# Airowl_Schematic.net
KiCad netlist of a schematic drawn in EAGLE
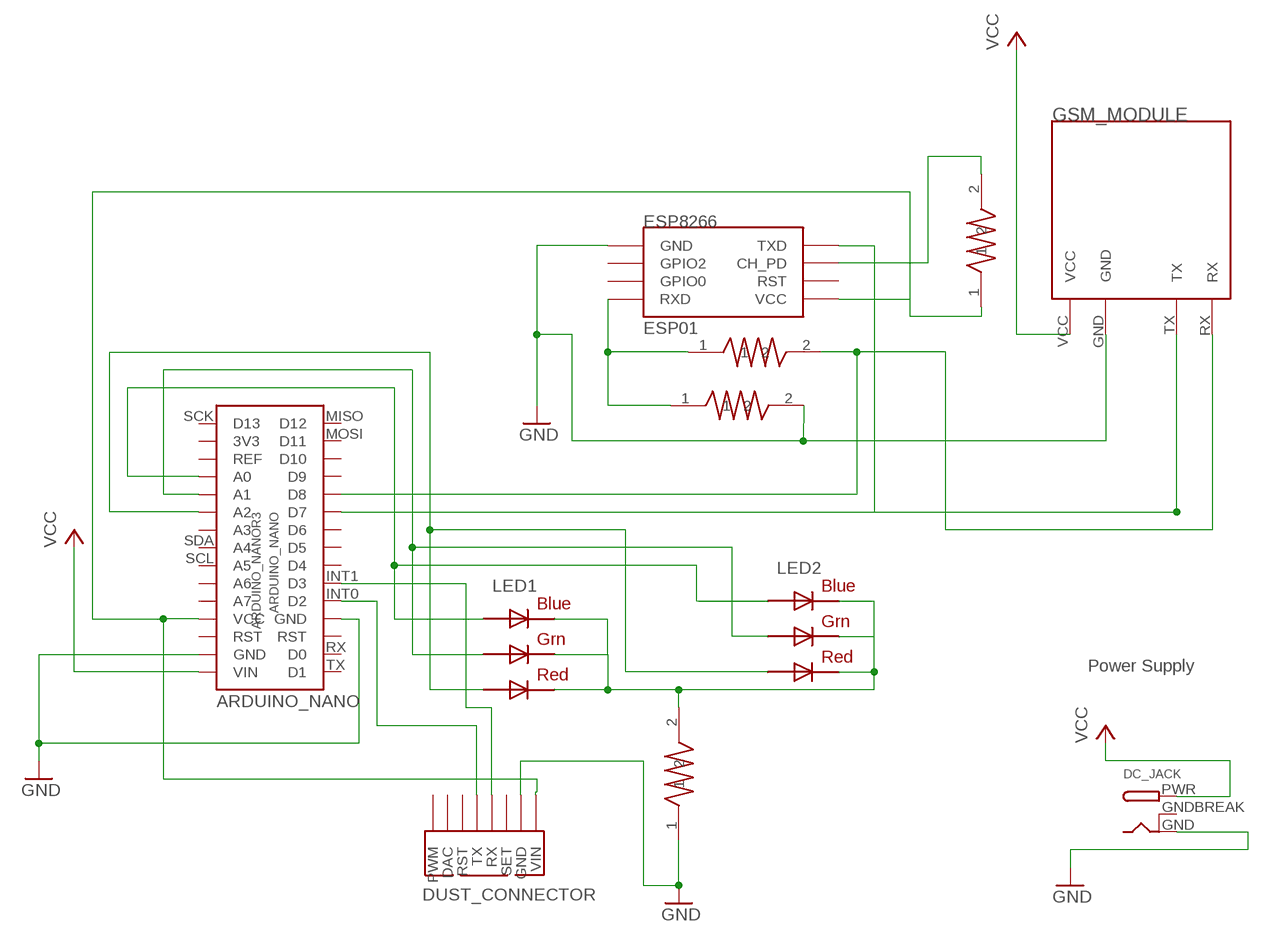
[diagram p0: schematic, sheet 1]

(export (version "E")
  (design (tool "Eeschema 10.0.6"))
  (components
    (comp (ref "ARDUINO_NANO")
      (value "ARDUINO_NANOR3")
      (footprint "eagle-import:ARDUINO-NANO")
      (libsource (lib "eagle-import") (part "ARDUINO_NANOR3"))
    )
    (comp (ref "DC_JACK")
      (value "DCBARRELPTH")
      (footprint "eagle-import:DCJACK_2MM_PTH")
      (libsource (lib "eagle-import") (part "DCBARRELPTH"))
    )
    (comp (ref "DUST_CONNECTOR")
      (value "WINSEN_CONNECTOR")
      (footprint "eagle-import:WINSEN_CONNECTOR")
      (libsource (lib "eagle-import") (part "WINSEN_CONNECTOR"))
    )
    (comp (ref "ESP8266")
      (value "ESP01")
      (footprint "eagle-import:ESP01")
      (libsource (lib "eagle-import") (part "ESP01"))
    )
    (comp (ref "GSM_MODULE")
      (value "GSM900_MODULE")
      (footprint "eagle-import:GSM900_MODULE")
      (libsource (lib "eagle-import") (part "GSM900_MODULE"))
    )
    (comp (ref "LED1")
      (value "RGBLED5050")
      (footprint "eagle-import:RGBLED5050")
      (libsource (lib "eagle-import") (part "RGBLED5050"))
    )
    (comp (ref "LED2")
      (value "RGBLED5050")
      (footprint "eagle-import:RGBLED5050")
      (libsource (lib "eagle-import") (part "RGBLED5050"))
    )
    (comp (ref "R1")
      (value "RESISTOR(HORIZONTAL)")
      (footprint "eagle-import:RESISTER(HORIZONTAL)")
      (libsource (lib "eagle-import") (part "RESISTOR(HORIZONTAL)"))
    )
    (comp (ref "R2")
      (value "RESISTOR(HORIZONTAL)")
      (footprint "eagle-import:RESISTER(HORIZONTAL)")
      (libsource (lib "eagle-import") (part "RESISTOR(HORIZONTAL)"))
    )
    (comp (ref "R3")
      (value "RESISTOR(HORIZONTAL)")
      (footprint "eagle-import:RESISTER(HORIZONTAL)")
      (libsource (lib "eagle-import") (part "RESISTOR(HORIZONTAL)"))
    )
    (comp (ref "R4")
      (value "RESISTOR(HORIZONTAL)")
      (footprint "eagle-import:RESISTER(HORIZONTAL)")
      (libsource (lib "eagle-import") (part "RESISTOR(HORIZONTAL)"))
    )
  )
  (nets
    (net (code "1") (name "/3V3") (class "Default")
      (node (ref "ARDUINO_NANO") (pin "3V3") (pinfunction "3V3_3V3") (pintype "power_in"))
    )
    (net (code "2") (name "/GNDBREAK") (class "Default")
      (node (ref "DC_JACK") (pin "GNDBREAK") (pinfunction "GNDBREAK_GNDBREAK") (pintype "power_in"))
    )
    (net (code "3") (name "GND") (class "Default")
      (node (ref "ARDUINO_NANO") (pin "GND@1") (pinfunction "GND_GND@1") (pintype "power_in"))
      (node (ref "ARDUINO_NANO") (pin "GND@2") (pinfunction "GND_GND@2") (pintype "power_in"))
      (node (ref "DC_JACK") (pin "GND") (pinfunction "GND_GND") (pintype "power_in"))
      (node (ref "DUST_CONNECTOR") (pin "P$8") (pinfunction "GND_P$8") (pintype "bidirectional"))
      (node (ref "ESP8266") (pin "GND") (pinfunction "GND_GND") (pintype "bidirectional"))
      (node (ref "GSM_MODULE") (pin "GND") (pinfunction "GND_GND") (pintype "bidirectional"))
      (node (ref "R1") (pin "1") (pinfunction "1_1") (pintype "bidirectional"))
      (node (ref "R3") (pin "2") (pinfunction "2_2") (pintype "bidirectional"))
    )
    (net (code "4") (name "Net-(ARDUINO_NANO-D2)") (class "Default")
      (node (ref "ARDUINO_NANO") (pin "INT0") (pinfunction "D2_INT0") (pintype "bidirectional"))
      (node (ref "DUST_CONNECTOR") (pin "P$5") (pinfunction "TX_P$5") (pintype "bidirectional"))
    )
    (net (code "5") (name "Net-(ARDUINO_NANO-D3)") (class "Default")
      (node (ref "ARDUINO_NANO") (pin "INT1") (pinfunction "D3_INT1") (pintype "bidirectional"))
      (node (ref "DUST_CONNECTOR") (pin "P$6") (pinfunction "RX_P$6") (pintype "bidirectional"))
    )
    (net (code "6") (name "Net-(ARDUINO_NANO-PadD8)") (class "Default")
      (node (ref "ARDUINO_NANO") (pin "D8") (pinfunction "D8_D8") (pintype "bidirectional"))
      (node (ref "GSM_MODULE") (pin "RX") (pinfunction "RX_RX") (pintype "bidirectional"))
      (node (ref "R2") (pin "2") (pinfunction "2_2") (pintype "bidirectional"))
    )
    (net (code "7") (name "Net-(DUST_CONNECTOR-VIN)") (class "Default")
      (node (ref "ARDUINO_NANO") (pin "VCC") (pinfunction "VCC_VCC") (pintype "power_in"))
      (node (ref "DUST_CONNECTOR") (pin "P$9") (pinfunction "VIN_P$9") (pintype "bidirectional"))
      (node (ref "ESP8266") (pin "VCC") (pinfunction "VCC_VCC") (pintype "bidirectional"))
      (node (ref "R4") (pin "1") (pinfunction "1_1") (pintype "bidirectional"))
    )
    (net (code "8") (name "Net-(ESP8266-PadCH_PD)") (class "Default")
      (node (ref "ESP8266") (pin "CH_PD") (pinfunction "CH_PD_CH_PD") (pintype "bidirectional"))
      (node (ref "R4") (pin "2") (pinfunction "2_2") (pintype "bidirectional"))
    )
    (net (code "9") (name "Net-(ESP8266-RXD)") (class "Default")
      (node (ref "ESP8266") (pin "RX") (pinfunction "RXD_RX") (pintype "bidirectional"))
      (node (ref "R2") (pin "1") (pinfunction "1_1") (pintype "bidirectional"))
      (node (ref "R3") (pin "1") (pinfunction "1_1") (pintype "bidirectional"))
    )
    (net (code "10") (name "Net-(ESP8266-TXD)") (class "Default")
      (node (ref "ARDUINO_NANO") (pin "D7") (pinfunction "D7_D7") (pintype "bidirectional"))
      (node (ref "ESP8266") (pin "TX") (pinfunction "TXD_TX") (pintype "bidirectional"))
      (node (ref "GSM_MODULE") (pin "TX") (pinfunction "TX_TX") (pintype "bidirectional"))
    )
    (net (code "11") (name "Net-(LED1-BLUE_A)") (class "Default")
      (node (ref "ARDUINO_NANO") (pin "A0") (pinfunction "A0_A0") (pintype "bidirectional"))
      (node (ref "LED1") (pin "3") (pinfunction "BLUE_A_3") (pintype "bidirectional"))
      (node (ref "LED2") (pin "3") (pinfunction "BLUE_A_3") (pintype "bidirectional"))
    )
    (net (code "12") (name "Net-(LED1-BLUE_C)") (class "Default")
      (node (ref "LED1") (pin "4") (pinfunction "BLUE_C_4") (pintype "bidirectional"))
      (node (ref "LED1") (pin "5") (pinfunction "RED_C_5") (pintype "bidirectional"))
      (node (ref "LED1") (pin "6") (pinfunction "GREEN_C_6") (pintype "bidirectional"))
      (node (ref "LED2") (pin "4") (pinfunction "BLUE_C_4") (pintype "bidirectional"))
      (node (ref "LED2") (pin "5") (pinfunction "RED_C_5") (pintype "bidirectional"))
      (node (ref "LED2") (pin "6") (pinfunction "GREEN_C_6") (pintype "bidirectional"))
    )
    (net (code "13") (name "Net-(LED1-GREEN_A)") (class "Default")
      (node (ref "ARDUINO_NANO") (pin "A1") (pinfunction "A1_A1") (pintype "bidirectional"))
      (node (ref "LED1") (pin "1") (pinfunction "GREEN_A_1") (pintype "bidirectional"))
      (node (ref "LED2") (pin "1") (pinfunction "GREEN_A_1") (pintype "bidirectional"))
    )
    (net (code "14") (name "Net-(LED1-RED_A)") (class "Default")
      (node (ref "ARDUINO_NANO") (pin "A2") (pinfunction "A2_A2") (pintype "bidirectional"))
      (node (ref "LED1") (pin "2") (pinfunction "RED_A_2") (pintype "bidirectional"))
      (node (ref "LED2") (pin "2") (pinfunction "RED_A_2") (pintype "bidirectional"))
    )
    (net (code "15") (name "VCC") (class "Default")
      (node (ref "ARDUINO_NANO") (pin "VIN") (pinfunction "VIN_VIN") (pintype "power_in"))
      (node (ref "DC_JACK") (pin "PWR") (pinfunction "PWR_PWR") (pintype "power_in"))
      (node (ref "GSM_MODULE") (pin "VCC") (pinfunction "VCC_VCC") (pintype "bidirectional"))
    )
    (net (code "16") (name "unconnected-(ARDUINO_NANO-A4-PadSDA)") (class "Default")
      (node (ref "ARDUINO_NANO") (pin "SDA") (pinfunction "A4_SDA") (pintype "bidirectional"))
    )
    (net (code "17") (name "unconnected-(ARDUINO_NANO-A5-PadSCL)") (class "Default")
      (node (ref "ARDUINO_NANO") (pin "SCL") (pinfunction "A5_SCL") (pintype "bidirectional"))
    )
    (net (code "18") (name "unconnected-(ARDUINO_NANO-D0-PadRX)") (class "Default")
      (node (ref "ARDUINO_NANO") (pin "RX") (pinfunction "D0_RX") (pintype "bidirectional"))
    )
    (net (code "19") (name "unconnected-(ARDUINO_NANO-D1-PadTX)") (class "Default")
      (node (ref "ARDUINO_NANO") (pin "TX") (pinfunction "D1_TX") (pintype "bidirectional"))
    )
    (net (code "20") (name "unconnected-(ARDUINO_NANO-D11-PadMOSI)") (class "Default")
      (node (ref "ARDUINO_NANO") (pin "MOSI") (pinfunction "D11_MOSI") (pintype "bidirectional"))
    )
    (net (code "21") (name "unconnected-(ARDUINO_NANO-D12-PadMISO)") (class "Default")
      (node (ref "ARDUINO_NANO") (pin "MISO") (pinfunction "D12_MISO") (pintype "bidirectional"))
    )
    (net (code "22") (name "unconnected-(ARDUINO_NANO-D13-PadSCK)") (class "Default")
      (node (ref "ARDUINO_NANO") (pin "SCK") (pinfunction "D13_SCK") (pintype "bidirectional"))
    )
    (net (code "23") (name "unconnected-(ARDUINO_NANO-PadA3)") (class "Default")
      (node (ref "ARDUINO_NANO") (pin "A3") (pinfunction "A3_A3") (pintype "bidirectional"))
    )
    (net (code "24") (name "unconnected-(ARDUINO_NANO-PadA6)") (class "Default")
      (node (ref "ARDUINO_NANO") (pin "A6") (pinfunction "A6_A6") (pintype "bidirectional"))
    )
    (net (code "25") (name "unconnected-(ARDUINO_NANO-PadA7)") (class "Default")
      (node (ref "ARDUINO_NANO") (pin "A7") (pinfunction "A7_A7") (pintype "bidirectional"))
    )
    (net (code "26") (name "unconnected-(ARDUINO_NANO-PadD4)") (class "Default")
      (node (ref "ARDUINO_NANO") (pin "D4") (pinfunction "D4_D4") (pintype "bidirectional"))
    )
    (net (code "27") (name "unconnected-(ARDUINO_NANO-PadD5)") (class "Default")
      (node (ref "ARDUINO_NANO") (pin "D5") (pinfunction "D5_D5") (pintype "bidirectional"))
    )
    (net (code "28") (name "unconnected-(ARDUINO_NANO-PadD6)") (class "Default")
      (node (ref "ARDUINO_NANO") (pin "D6") (pinfunction "D6_D6") (pintype "bidirectional"))
    )
    (net (code "29") (name "unconnected-(ARDUINO_NANO-PadD9)") (class "Default")
      (node (ref "ARDUINO_NANO") (pin "D9") (pinfunction "D9_D9") (pintype "bidirectional"))
    )
    (net (code "30") (name "unconnected-(ARDUINO_NANO-PadD10)") (class "Default")
      (node (ref "ARDUINO_NANO") (pin "D10") (pinfunction "D10_D10") (pintype "bidirectional"))
    )
    (net (code "31") (name "unconnected-(ARDUINO_NANO-PadREF)") (class "Default")
      (node (ref "ARDUINO_NANO") (pin "REF") (pinfunction "REF_REF") (pintype "bidirectional"))
    )
    (net (code "32") (name "unconnected-(ARDUINO_NANO-RST-PadRST@1)") (class "Default")
      (node (ref "ARDUINO_NANO") (pin "RST@1") (pinfunction "RST_RST@1") (pintype "bidirectional"))
    )
    (net (code "33") (name "unconnected-(ARDUINO_NANO-RST-PadRST@2)") (class "Default")
      (node (ref "ARDUINO_NANO") (pin "RST@2") (pinfunction "RST_RST@2") (pintype "bidirectional"))
    )
    (net (code "34") (name "unconnected-(DUST_CONNECTOR-DAC-PadP$3)") (class "Default")
      (node (ref "DUST_CONNECTOR") (pin "P$3") (pinfunction "DAC_P$3") (pintype "bidirectional"))
    )
    (net (code "35") (name "unconnected-(DUST_CONNECTOR-PWM-PadP$2)") (class "Default")
      (node (ref "DUST_CONNECTOR") (pin "P$2") (pinfunction "PWM_P$2") (pintype "bidirectional"))
    )
    (net (code "36") (name "unconnected-(DUST_CONNECTOR-RST-PadP$4)") (class "Default")
      (node (ref "DUST_CONNECTOR") (pin "P$4") (pinfunction "RST_P$4") (pintype "bidirectional"))
    )
    (net (code "37") (name "unconnected-(DUST_CONNECTOR-SET-PadP$7)") (class "Default")
      (node (ref "DUST_CONNECTOR") (pin "P$7") (pinfunction "SET_P$7") (pintype "bidirectional"))
    )
    (net (code "38") (name "unconnected-(ESP8266-PadGPIO0)") (class "Default")
      (node (ref "ESP8266") (pin "GPIO0") (pinfunction "GPIO0_GPIO0") (pintype "bidirectional"))
    )
    (net (code "39") (name "unconnected-(ESP8266-PadGPIO2)") (class "Default")
      (node (ref "ESP8266") (pin "GPIO2") (pinfunction "GPIO2_GPIO2") (pintype "bidirectional"))
    )
    (net (code "40") (name "unconnected-(ESP8266-PadRST)") (class "Default")
      (node (ref "ESP8266") (pin "RST") (pinfunction "RST_RST") (pintype "bidirectional"))
    )
    (net (code "41") (name "unconnected-(R1-Pad2)") (class "Default")
      (node (ref "R1") (pin "2") (pinfunction "2_2") (pintype "bidirectional"))
    )
  )
)
